# UART2.net
KiCad netlist of a schematic drawn in Altium Designer
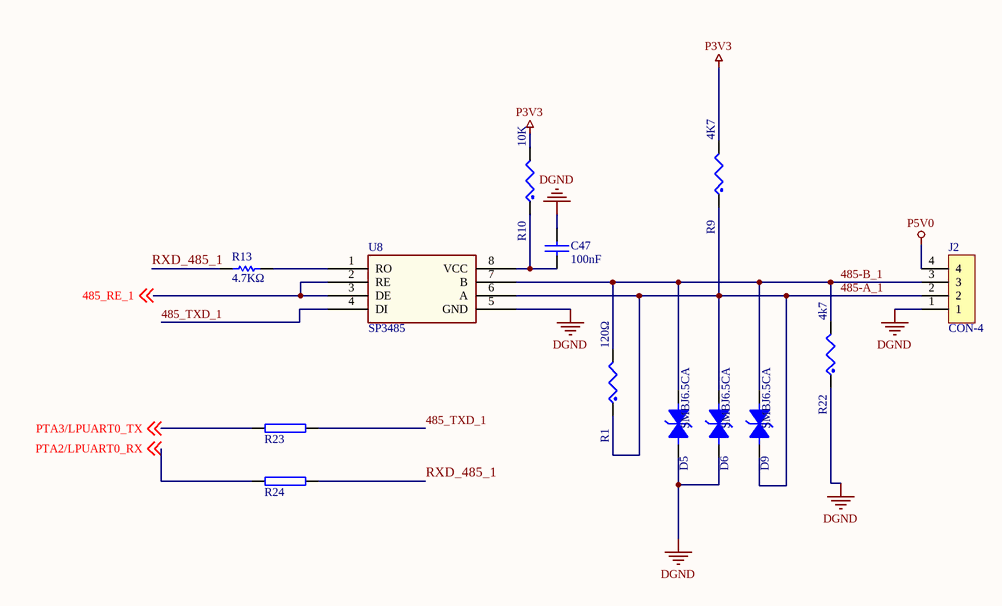
[diagram p0: UART2.SchDoc]

(export (version "E")
  (design (tool "Eeschema 10.0.6"))
  (components
    (comp (ref "C47")
      (value "100nF")
      (footprint "CC0402_25")
      (description "Capacitor")
      (libsource (lib "TAG_ZYWB") (part "CAP"))
    )
    (comp (ref "D5") (value "SMBJ6.5CA") (footprint "1812") (libsource (lib "TAG_ZYWB") (part "BV05C")))
    (comp (ref "D6") (value "SMBJ6.5CA") (footprint "1812") (libsource (lib "TAG_ZYWB") (part "BV05C")))
    (comp (ref "D9") (value "SMBJ6.5CA") (footprint "1812") (libsource (lib "TAG_ZYWB") (part "BV05C")))
    (comp (ref "J2")
      (value "CON-4")
      (footprint "GSP003RC-4-3.5")
      (libsource (lib "所控显示20180528") (part "CON-4"))
    )
    (comp (ref "R1")
      (value "120Ω")
      (footprint "RC0603_OV")
      (description "RES MF ZERO OHM 1/10W -- 0603")
      (libsource (lib "*") (part "RES"))
    )
    (comp (ref "R9")
      (value "4K7")
      (footprint "RC0603_OV")
      (description "RES MF ZERO OHM 1/10W -- 0603")
      (libsource (lib "*") (part "RES"))
    )
    (comp (ref "R10")
      (value "10K")
      (footprint "RC0603_OV")
      (description "RES MF ZERO OHM 1/10W -- 0603")
      (libsource (lib "*") (part "RES"))
    )
    (comp (ref "R13")
      (value "4.7KΩ")
      (footprint "R0402")
      (description "Resistor")
      (fields (field (name "PUBLISHER") "Altium Limited"))
      (libsource (lib "PCB_Project_1") (part "Res1"))
    )
    (comp (ref "R22")
      (value "4k7")
      (footprint "RC0603_OV")
      (description "RES MF ZERO OHM 1/10W -- 0603")
      (libsource (lib "*") (part "RES"))
    )
    (comp (ref "R23")
      (value "0")
      (footprint "RC0402_25")
      (libsource (lib "STM32F103C8T6+RC523") (part "RES2"))
    )
    (comp (ref "R24")
      (value "0")
      (footprint "RC0402_25")
      (libsource (lib "STM32F103C8T6+RC523") (part "RES2"))
    )
    (comp (ref "U8") (value "SP3485") (footprint "SOP-8") (libsource (lib "TAG_ZYWB") (part "SP3485")))
  )
  (nets
    (net (code "1") (name "/485-A_1") (class "Default")
      (node (ref "D6") (pin "2") (pinfunction "ANODE_2") (pintype "passive"))
      (node (ref "D9") (pin "1") (pinfunction "CATHODE_1") (pintype "passive"))
      (node (ref "J2") (pin "2") (pinfunction "2_2") (pintype "passive"))
      (node (ref "R1") (pin "1") (pinfunction "1_1") (pintype "passive"))
      (node (ref "R9") (pin "1") (pinfunction "1_1") (pintype "passive"))
      (node (ref "U8") (pin "6") (pinfunction "A_6") (pintype "passive"))
    )
    (net (code "2") (name "/485-B_1") (class "Default")
      (node (ref "D5") (pin "2") (pinfunction "ANODE_2") (pintype "passive"))
      (node (ref "D9") (pin "2") (pinfunction "ANODE_2") (pintype "passive"))
      (node (ref "J2") (pin "3") (pinfunction "3_3") (pintype "passive"))
      (node (ref "R1") (pin "2") (pinfunction "2_2") (pintype "passive"))
      (node (ref "R22") (pin "2") (pinfunction "2_2") (pintype "passive"))
      (node (ref "U8") (pin "7") (pinfunction "B_7") (pintype "passive"))
    )
    (net (code "3") (name "/485_TXD_1") (class "Default")
      (node (ref "R23") (pin "1") (pinfunction "1_1") (pintype "passive"))
      (node (ref "U8") (pin "4") (pinfunction "DI_4") (pintype "passive"))
    )
    (net (code "4") (name "/RXD_485_1") (class "Default")
      (node (ref "R13") (pin "2") (pinfunction "2_2") (pintype "passive"))
      (node (ref "R24") (pin "1") (pinfunction "1_1") (pintype "passive"))
    )
    (net (code "5") (name "485_RE_1") (class "Default")
      (node (ref "U8") (pin "2") (pinfunction "RE_2") (pintype "passive"))
      (node (ref "U8") (pin "3") (pinfunction "DE_3") (pintype "passive"))
    )
    (net (code "6") (name "DGND") (class "Default")
      (node (ref "C47") (pin "2") (pinfunction "2_2") (pintype "passive"))
      (node (ref "D5") (pin "1") (pinfunction "CATHODE_1") (pintype "passive"))
      (node (ref "D6") (pin "1") (pinfunction "CATHODE_1") (pintype "passive"))
      (node (ref "J2") (pin "1") (pinfunction "1_1") (pintype "passive"))
      (node (ref "R22") (pin "1") (pinfunction "1_1") (pintype "passive"))
      (node (ref "U8") (pin "5") (pinfunction "GND_5") (pintype "passive"))
    )
    (net (code "7") (name "Net-(U8-RO)") (class "Default")
      (node (ref "R13") (pin "1") (pinfunction "1_1") (pintype "passive"))
      (node (ref "U8") (pin "1") (pinfunction "RO_1") (pintype "passive"))
    )
    (net (code "8") (name "Net-(U8-VCC)") (class "Default")
      (node (ref "C47") (pin "1") (pinfunction "1_1") (pintype "passive"))
      (node (ref "R10") (pin "1") (pinfunction "1_1") (pintype "passive"))
      (node (ref "U8") (pin "8") (pinfunction "VCC_8") (pintype "passive"))
    )
    (net (code "9") (name "P3V3") (class "Default")
      (node (ref "R10") (pin "2") (pinfunction "2_2") (pintype "passive"))
      (node (ref "R9") (pin "2") (pinfunction "2_2") (pintype "passive"))
    )
    (net (code "10") (name "P5V0") (class "Default")
      (node (ref "J2") (pin "4") (pinfunction "4_4") (pintype "passive"))
    )
    (net (code "11") (name "PTA2{slash}LPUART0_RX") (class "Default")
      (node (ref "R24") (pin "2") (pinfunction "2_2") (pintype "passive"))
    )
    (net (code "12") (name "PTA3{slash}LPUART0_TX") (class "Default")
      (node (ref "R23") (pin "2") (pinfunction "2_2") (pintype "passive"))
    )
  )
)
